# m2_emmc.net
KiCad netlist of a schematic drawn in Altium Designer
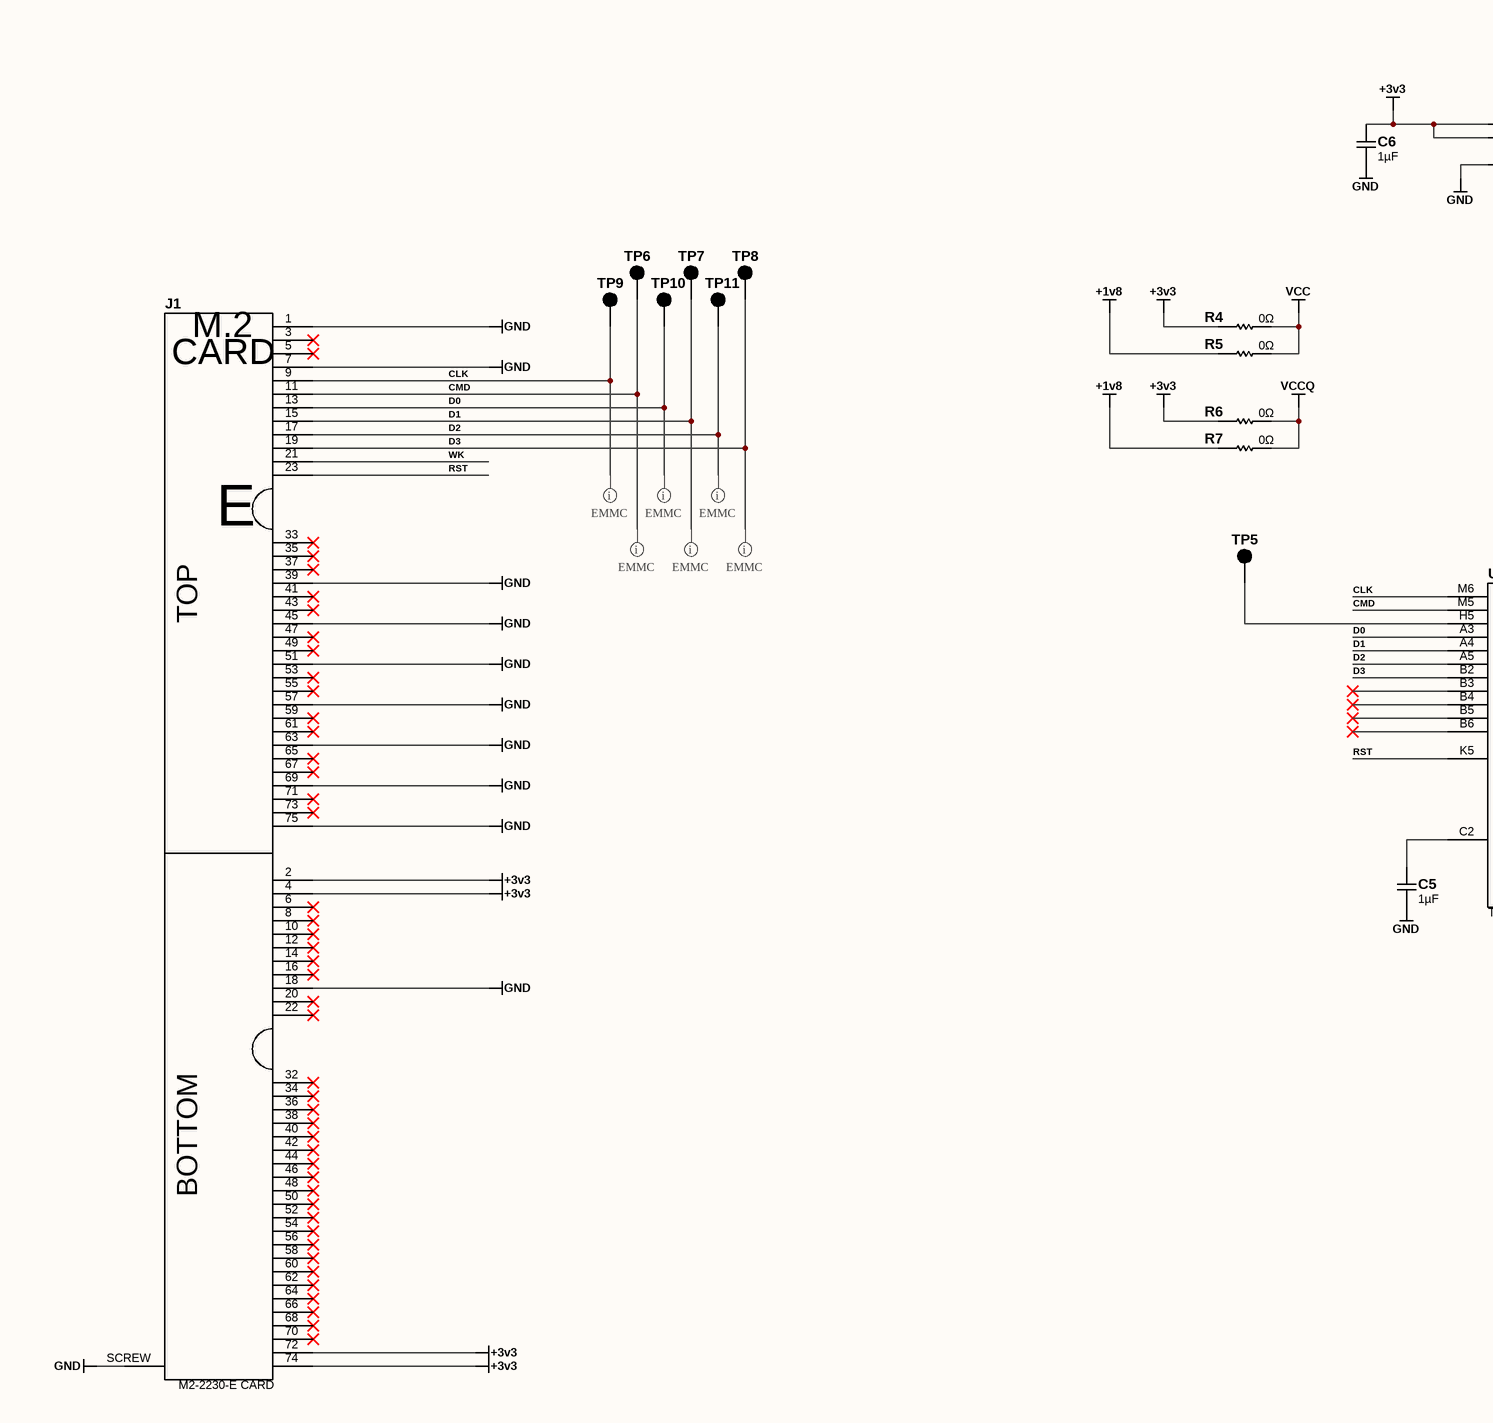
[diagram p0: m2_emmc.SchDoc, top left]
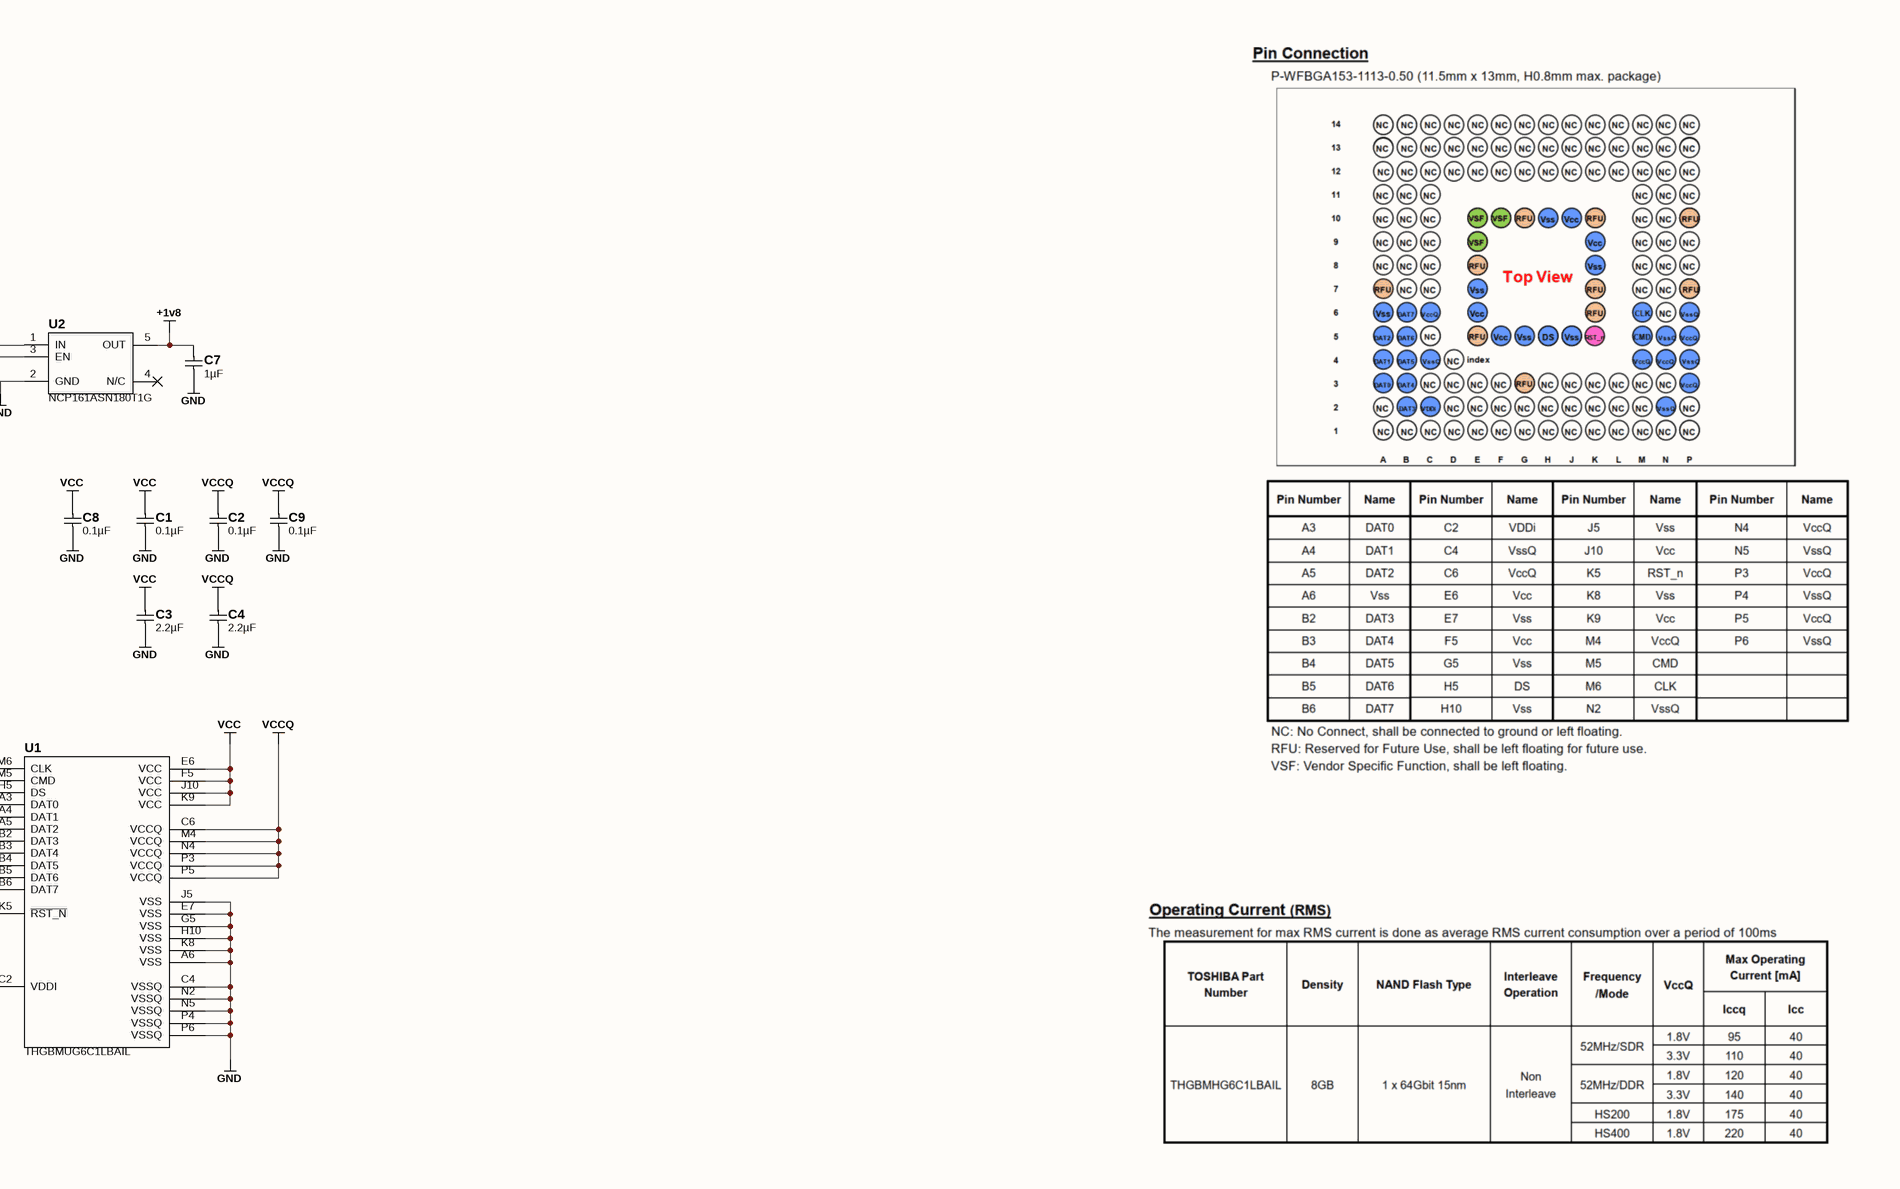
[diagram p1: m2_emmc.SchDoc, top right]
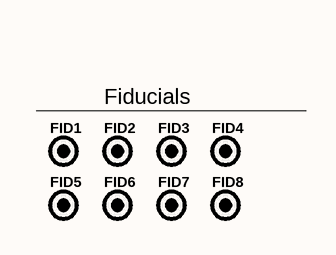
[diagram p2: m2_emmc.SchDoc, bottom left]
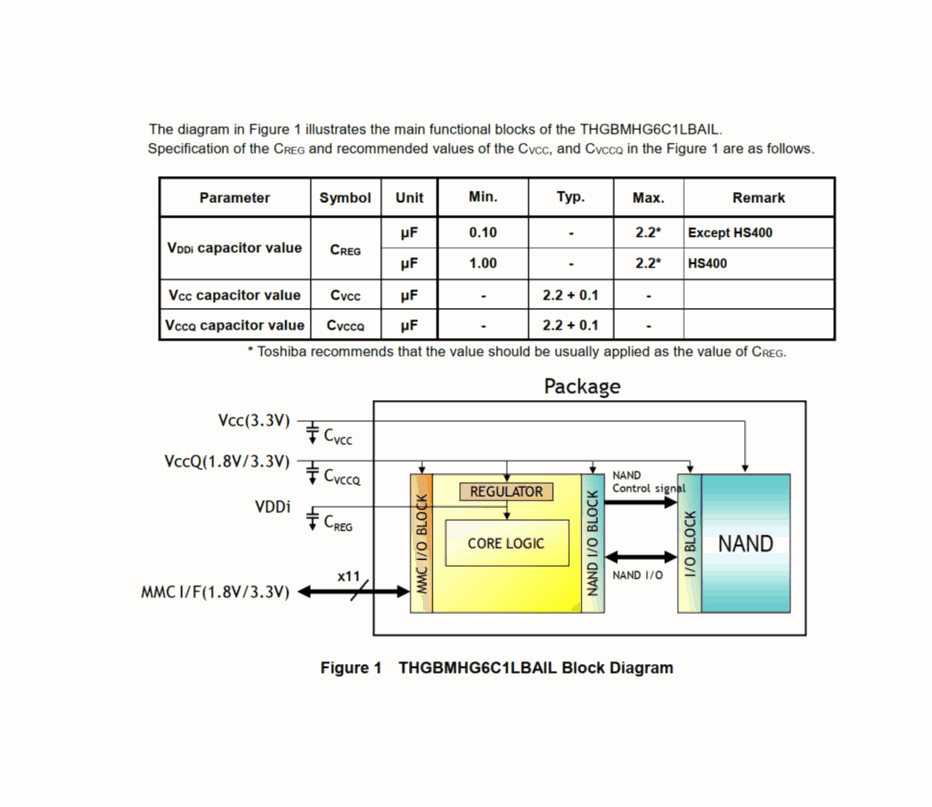
[diagram p3: m2_emmc.SchDoc, bottom right]

(export (version "E")
  (design (tool "Eeschema 10.0.6"))
  (components
    (comp (ref "C1")
      (value "0.1µF")
      (footprint "C0603_0.90MM_HD")
      (description "CAP CER 0.1UF 16V X7R 0603")
      (fields (field (name "INTERNAL PART NUMBER") "nan") (field (name "MANUFACTURER") "Murata Electronics"))
      (libsource (lib "capacitors") (part "C_2P_NP"))
    )
    (comp (ref "C2")
      (value "0.1µF")
      (footprint "C0603_0.90MM_HD")
      (description "CAP CER 0.1UF 16V X7R 0603")
      (fields (field (name "INTERNAL PART NUMBER") "nan") (field (name "MANUFACTURER") "Murata Electronics"))
      (libsource (lib "capacitors") (part "C_2P_NP"))
    )
    (comp (ref "C3")
      (value "2.2µF")
      (footprint "C0603_0.90MM_HD")
      (description "CAP CER 2.2UF 6.3V X7R 0603")
      (fields (field (name "INTERNAL PART NUMBER") "nan") (field (name "MANUFACTURER") "Murata Electronics"))
      (libsource (lib "capacitors") (part "C_2P_NP"))
    )
    (comp (ref "C4")
      (value "2.2µF")
      (footprint "C0603_0.90MM_HD")
      (description "CAP CER 2.2UF 6.3V X7R 0603")
      (fields (field (name "INTERNAL PART NUMBER") "nan") (field (name "MANUFACTURER") "Murata Electronics"))
      (libsource (lib "capacitors") (part "C_2P_NP"))
    )
    (comp (ref "C5")
      (value "1µF")
      (footprint "C0603_0.90MM_HD")
      (description "CAP CER 1UF 16V X7R 0603")
      (fields (field (name "INTERNAL PART NUMBER") "nan") (field (name "MANUFACTURER") "Murata Electronics"))
      (libsource (lib "capacitors") (part "C_2P_NP"))
    )
    (comp (ref "C6")
      (value "1µF")
      (footprint "C0603_0.90MM_HD")
      (description "CAP CER 1UF 16V X7R 0603")
      (fields (field (name "INTERNAL PART NUMBER") "nan") (field (name "MANUFACTURER") "Murata Electronics"))
      (libsource (lib "capacitors") (part "C_2P_NP"))
    )
    (comp (ref "C7")
      (value "1µF")
      (footprint "C0603_0.90MM_HD")
      (description "CAP CER 1UF 16V X7R 0603")
      (fields (field (name "INTERNAL PART NUMBER") "nan") (field (name "MANUFACTURER") "Murata Electronics"))
      (libsource (lib "capacitors") (part "C_2P_NP"))
    )
    (comp (ref "C8")
      (value "0.1µF")
      (footprint "C0603_0.90MM_HD")
      (description "CAP CER 0.1UF 16V X7R 0603")
      (fields (field (name "INTERNAL PART NUMBER") "nan") (field (name "MANUFACTURER") "Murata Electronics"))
      (libsource (lib "capacitors") (part "C_2P_NP"))
    )
    (comp (ref "C9")
      (value "0.1µF")
      (footprint "C0603_0.90MM_HD")
      (description "CAP CER 0.1UF 16V X7R 0603")
      (fields (field (name "INTERNAL PART NUMBER") "nan") (field (name "MANUFACTURER") "Murata Electronics"))
      (libsource (lib "capacitors") (part "C_2P_NP"))
    )
    (comp (ref "FID1")
      (value "fiducial-1mm-2mm")
      (footprint "fiducial-1mm-2mm")
      (fields (field (name "MANUFACTURER") "Wavenumber"))
      (libsource (lib "misc") (part "Fiducial"))
    )
    (comp (ref "FID2")
      (value "fiducial-1mm-2mm")
      (footprint "fiducial-1mm-2mm")
      (fields (field (name "MANUFACTURER") "Wavenumber"))
      (libsource (lib "misc") (part "Fiducial"))
    )
    (comp (ref "FID3")
      (value "fiducial-1mm-2mm")
      (footprint "fiducial-1mm-2mm")
      (fields (field (name "MANUFACTURER") "Wavenumber"))
      (libsource (lib "misc") (part "Fiducial"))
    )
    (comp (ref "FID4")
      (value "fiducial-1mm-2mm")
      (footprint "fiducial-1mm-2mm")
      (fields (field (name "MANUFACTURER") "Wavenumber"))
      (libsource (lib "misc") (part "Fiducial"))
    )
    (comp (ref "FID5")
      (value "fiducial-1mm-2mm")
      (footprint "fiducial-1mm-2mm")
      (fields (field (name "MANUFACTURER") "Wavenumber"))
      (libsource (lib "misc") (part "Fiducial"))
    )
    (comp (ref "FID6")
      (value "fiducial-1mm-2mm")
      (footprint "fiducial-1mm-2mm")
      (fields (field (name "MANUFACTURER") "Wavenumber"))
      (libsource (lib "misc") (part "Fiducial"))
    )
    (comp (ref "FID7")
      (value "fiducial-1mm-2mm")
      (footprint "fiducial-1mm-2mm")
      (fields (field (name "MANUFACTURER") "Wavenumber"))
      (libsource (lib "misc") (part "Fiducial"))
    )
    (comp (ref "FID8")
      (value "fiducial-1mm-2mm")
      (footprint "fiducial-1mm-2mm")
      (fields (field (name "MANUFACTURER") "Wavenumber"))
      (libsource (lib "misc") (part "Fiducial"))
    )
    (comp (ref "J1")
      (value "M2-2230-E CARD")
      (footprint "M2-2230-E")
      (description "M.2 2230 E Key Card Template")
      (fields (field (name "MANUFACTURER") "Wavenumber"))
      (libsource (lib "module") (part "M2_CARD__E"))
    )
    (comp (ref "R4")
      (value "0Ω")
      (footprint "R0603_0.55MM_HD")
      (description "RES 0.0 OHM 1/10W JUMP 0603 SMD")
      (fields
        (field (name "INTERNAL PART NUMBER") "nan")
        (field (name "MANUFACTURER") "Panasonic Electronic Components")
      )
      (libsource (lib "resistor_jellybean") (part "R_2P"))
    )
    (comp (ref "R5")
      (value "0Ω")
      (footprint "R0603_0.55MM_HD")
      (description "RES 0.0 OHM 1/10W JUMP 0603 SMD")
      (fields
        (field (name "INTERNAL PART NUMBER") "nan")
        (field (name "MANUFACTURER") "Panasonic Electronic Components")
      )
      (libsource (lib "resistor_jellybean") (part "R_2P"))
    )
    (comp (ref "R6")
      (value "0Ω")
      (footprint "R0603_0.55MM_HD")
      (description "RES 0.0 OHM 1/10W JUMP 0603 SMD")
      (fields
        (field (name "INTERNAL PART NUMBER") "nan")
        (field (name "MANUFACTURER") "Panasonic Electronic Components")
      )
      (libsource (lib "resistor_jellybean") (part "R_2P"))
    )
    (comp (ref "R7")
      (value "0Ω")
      (footprint "R0603_0.55MM_HD")
      (description "RES 0.0 OHM 1/10W JUMP 0603 SMD")
      (fields
        (field (name "INTERNAL PART NUMBER") "nan")
        (field (name "MANUFACTURER") "Panasonic Electronic Components")
      )
      (libsource (lib "resistor_jellybean") (part "R_2P"))
    )
    (comp (ref "TP5")
      (value "SMT Testpoint 20mil")
      (footprint "SMT_TP-25")
      (fields
        (field (name "MANUFACTURER PART NUMBER") "SMT_TP-25")
        (field (name "MANUFACTURER") "Wavenumber")
      )
      (libsource (lib "misc") (part "SMT_TEST"))
    )
    (comp (ref "TP6")
      (value "SMT Testpoint 20mil")
      (footprint "SMT_TP-25")
      (fields
        (field (name "MANUFACTURER PART NUMBER") "SMT_TP-25")
        (field (name "MANUFACTURER") "Wavenumber")
      )
      (libsource (lib "misc") (part "SMT_TEST"))
    )
    (comp (ref "TP7")
      (value "SMT Testpoint 20mil")
      (footprint "SMT_TP-25")
      (fields
        (field (name "MANUFACTURER PART NUMBER") "SMT_TP-25")
        (field (name "MANUFACTURER") "Wavenumber")
      )
      (libsource (lib "misc") (part "SMT_TEST"))
    )
    (comp (ref "TP8")
      (value "SMT Testpoint 20mil")
      (footprint "SMT_TP-25")
      (fields
        (field (name "MANUFACTURER PART NUMBER") "SMT_TP-25")
        (field (name "MANUFACTURER") "Wavenumber")
      )
      (libsource (lib "misc") (part "SMT_TEST"))
    )
    (comp (ref "TP9")
      (value "SMT Testpoint 20mil")
      (footprint "SMT_TP-25")
      (fields
        (field (name "MANUFACTURER PART NUMBER") "SMT_TP-25")
        (field (name "MANUFACTURER") "Wavenumber")
      )
      (libsource (lib "misc") (part "SMT_TEST"))
    )
    (comp (ref "TP10")
      (value "SMT Testpoint 20mil")
      (footprint "SMT_TP-25")
      (fields
        (field (name "MANUFACTURER PART NUMBER") "SMT_TP-25")
        (field (name "MANUFACTURER") "Wavenumber")
      )
      (libsource (lib "misc") (part "SMT_TEST"))
    )
    (comp (ref "TP11")
      (value "SMT Testpoint 20mil")
      (footprint "SMT_TP-25")
      (fields
        (field (name "MANUFACTURER PART NUMBER") "SMT_TP-25")
        (field (name "MANUFACTURER") "Wavenumber")
      )
      (libsource (lib "misc") (part "SMT_TEST"))
    )
    (comp (ref "U1")
      (value "THGBMUG6C1LBAIL")
      (footprint "BGA153C50P14X14_1150X1300X80")
      (description "eMMC 8GB v5.1 eMMC")
      (fields
        (field (name "MANUFACTURER") "Kioxia America")
        (field (name "JLCPCB PART #") "C7509349")
        (field (name "CREATED BY") "JSA")
      )
      (libsource (lib "ic") (part "EMMC-Generic"))
    )
    (comp (ref "U2")
      (value "NCP161ASN180T1G")
      (footprint "SOT23-5")
      (description "IC REG LINEAR 1.8V 450MA SOT23-5")
      (fields (field (name "MANUFACTURER") "onsemi") (field (name "JLCPCB PART #") "C22435172"))
      (libsource (lib "ic") (part "NCP161"))
    )
  )
  (nets
    (net (code "1") (name "+1v8") (class "Default")
      (node (ref "C7") (pin "2") (pinfunction "1_2") (pintype "passive"))
      (node (ref "R5") (pin "1") (pinfunction "1_1") (pintype "passive"))
      (node (ref "R7") (pin "1") (pinfunction "1_1") (pintype "passive"))
      (node (ref "U2") (pin "5") (pinfunction "OUT_5") (pintype "passive"))
    )
    (net (code "2") (name "+3v3") (class "Default")
      (node (ref "C6") (pin "2") (pinfunction "1_2") (pintype "passive"))
      (node (ref "J1") (pin "2") (pinfunction "2_2") (pintype "passive"))
      (node (ref "J1") (pin "4") (pinfunction "4_4") (pintype "passive"))
      (node (ref "J1") (pin "72") (pinfunction "72_72") (pintype "passive"))
      (node (ref "J1") (pin "74") (pinfunction "74_74") (pintype "passive"))
      (node (ref "R4") (pin "1") (pinfunction "1_1") (pintype "passive"))
      (node (ref "R6") (pin "1") (pinfunction "1_1") (pintype "passive"))
      (node (ref "U2") (pin "1") (pinfunction "IN_1") (pintype "passive"))
      (node (ref "U2") (pin "3") (pinfunction "EN_3") (pintype "passive"))
    )
    (net (code "3") (name "/CLK") (class "Default")
      (node (ref "J1") (pin "9") (pinfunction "9_9") (pintype "passive"))
      (node (ref "TP9") (pin "1") (pinfunction "1_1") (pintype "passive"))
      (node (ref "U1") (pin "M6") (pinfunction "CLK_M6") (pintype "passive"))
    )
    (net (code "4") (name "/CMD") (class "Default")
      (node (ref "J1") (pin "11") (pinfunction "11_11") (pintype "passive"))
      (node (ref "TP6") (pin "1") (pinfunction "1_1") (pintype "passive"))
      (node (ref "U1") (pin "M5") (pinfunction "CMD_M5") (pintype "passive"))
    )
    (net (code "5") (name "/D0") (class "Default")
      (node (ref "J1") (pin "13") (pinfunction "13_13") (pintype "passive"))
      (node (ref "TP10") (pin "1") (pinfunction "1_1") (pintype "passive"))
      (node (ref "U1") (pin "A3") (pinfunction "DAT0_A3") (pintype "passive"))
    )
    (net (code "6") (name "/D1") (class "Default")
      (node (ref "J1") (pin "15") (pinfunction "15_15") (pintype "passive"))
      (node (ref "TP7") (pin "1") (pinfunction "1_1") (pintype "passive"))
      (node (ref "U1") (pin "A4") (pinfunction "DAT1_A4") (pintype "passive"))
    )
    (net (code "7") (name "/D2") (class "Default")
      (node (ref "J1") (pin "17") (pinfunction "17_17") (pintype "passive"))
      (node (ref "TP11") (pin "1") (pinfunction "1_1") (pintype "passive"))
      (node (ref "U1") (pin "A5") (pinfunction "DAT2_A5") (pintype "passive"))
    )
    (net (code "8") (name "/D3") (class "Default")
      (node (ref "J1") (pin "19") (pinfunction "19_19") (pintype "passive"))
      (node (ref "TP8") (pin "1") (pinfunction "1_1") (pintype "passive"))
      (node (ref "U1") (pin "B2") (pinfunction "DAT3_B2") (pintype "passive"))
    )
    (net (code "9") (name "/RST") (class "Default")
      (node (ref "J1") (pin "23") (pinfunction "23_23") (pintype "passive"))
      (node (ref "U1") (pin "K5") (pinfunction "~{RST_N}_K5") (pintype "passive"))
    )
    (net (code "10") (name "/WK") (class "Default")
      (node (ref "J1") (pin "21") (pinfunction "21_21") (pintype "passive"))
    )
    (net (code "11") (name "GND") (class "Default")
      (node (ref "C1") (pin "1") (pinfunction "1_1") (pintype "passive"))
      (node (ref "C2") (pin "1") (pinfunction "1_1") (pintype "passive"))
      (node (ref "C3") (pin "1") (pinfunction "1_1") (pintype "passive"))
      (node (ref "C4") (pin "1") (pinfunction "1_1") (pintype "passive"))
      (node (ref "C5") (pin "1") (pinfunction "1_1") (pintype "passive"))
      (node (ref "C6") (pin "1") (pinfunction "1_1") (pintype "passive"))
      (node (ref "C7") (pin "1") (pinfunction "1_1") (pintype "passive"))
      (node (ref "C8") (pin "1") (pinfunction "1_1") (pintype "passive"))
      (node (ref "C9") (pin "1") (pinfunction "1_1") (pintype "passive"))
      (node (ref "J1") (pin "1") (pinfunction "1_1") (pintype "passive"))
      (node (ref "J1") (pin "18") (pinfunction "18_18") (pintype "passive"))
      (node (ref "J1") (pin "39") (pinfunction "39_39") (pintype "passive"))
      (node (ref "J1") (pin "45") (pinfunction "45_45") (pintype "passive"))
      (node (ref "J1") (pin "51") (pinfunction "51_51") (pintype "passive"))
      (node (ref "J1") (pin "57") (pinfunction "57_57") (pintype "passive"))
      (node (ref "J1") (pin "63") (pinfunction "63_63") (pintype "passive"))
      (node (ref "J1") (pin "69") (pinfunction "69_69") (pintype "passive"))
      (node (ref "J1") (pin "7") (pinfunction "7_7") (pintype "passive"))
      (node (ref "J1") (pin "75") (pinfunction "75_75") (pintype "passive"))
      (node (ref "J1") (pin "SCREW") (pinfunction "SCREW_SCREW") (pintype "passive"))
      (node (ref "U1") (pin "A6") (pinfunction "VSS_A6") (pintype "passive"))
      (node (ref "U1") (pin "C4") (pinfunction "VSSQ_C4") (pintype "passive"))
      (node (ref "U1") (pin "E7") (pinfunction "VSS_E7") (pintype "passive"))
      (node (ref "U1") (pin "G5") (pinfunction "VSS_G5") (pintype "passive"))
      (node (ref "U1") (pin "H10") (pinfunction "VSS_H10") (pintype "passive"))
      (node (ref "U1") (pin "J5") (pinfunction "VSS_J5") (pintype "passive"))
      (node (ref "U1") (pin "K8") (pinfunction "VSS_K8") (pintype "passive"))
      (node (ref "U1") (pin "N2") (pinfunction "VSSQ_N2") (pintype "passive"))
      (node (ref "U1") (pin "N5") (pinfunction "VSSQ_N5") (pintype "passive"))
      (node (ref "U1") (pin "P4") (pinfunction "VSSQ_P4") (pintype "passive"))
      (node (ref "U1") (pin "P6") (pinfunction "VSSQ_P6") (pintype "passive"))
      (node (ref "U2") (pin "2") (pinfunction "GND_2") (pintype "passive"))
    )
    (net (code "12") (name "Net-(U1-DS)") (class "Default")
      (node (ref "TP5") (pin "1") (pinfunction "1_1") (pintype "passive"))
      (node (ref "U1") (pin "H5") (pinfunction "DS_H5") (pintype "passive"))
    )
    (net (code "13") (name "Net-(U1-VDDI)") (class "Default")
      (node (ref "C5") (pin "2") (pinfunction "1_2") (pintype "passive"))
      (node (ref "U1") (pin "C2") (pinfunction "VDDI_C2") (pintype "passive"))
    )
    (net (code "14") (name "VCC") (class "Default")
      (node (ref "C1") (pin "2") (pinfunction "1_2") (pintype "passive"))
      (node (ref "C3") (pin "2") (pinfunction "1_2") (pintype "passive"))
      (node (ref "C8") (pin "2") (pinfunction "1_2") (pintype "passive"))
      (node (ref "R4") (pin "2") (pinfunction "2_2") (pintype "passive"))
      (node (ref "R5") (pin "2") (pinfunction "2_2") (pintype "passive"))
      (node (ref "U1") (pin "E6") (pinfunction "VCC_E6") (pintype "passive"))
      (node (ref "U1") (pin "F5") (pinfunction "VCC_F5") (pintype "passive"))
      (node (ref "U1") (pin "J10") (pinfunction "VCC_J10") (pintype "passive"))
      (node (ref "U1") (pin "K9") (pinfunction "VCC_K9") (pintype "passive"))
    )
    (net (code "15") (name "VCCQ") (class "Default")
      (node (ref "C2") (pin "2") (pinfunction "1_2") (pintype "passive"))
      (node (ref "C4") (pin "2") (pinfunction "1_2") (pintype "passive"))
      (node (ref "C9") (pin "2") (pinfunction "1_2") (pintype "passive"))
      (node (ref "R6") (pin "2") (pinfunction "2_2") (pintype "passive"))
      (node (ref "R7") (pin "2") (pinfunction "2_2") (pintype "passive"))
      (node (ref "U1") (pin "C6") (pinfunction "VCCQ_C6") (pintype "passive"))
      (node (ref "U1") (pin "M4") (pinfunction "VCCQ_M4") (pintype "passive"))
      (node (ref "U1") (pin "N4") (pinfunction "VCCQ_N4") (pintype "passive"))
      (node (ref "U1") (pin "P3") (pinfunction "VCCQ_P3") (pintype "passive"))
      (node (ref "U1") (pin "P5") (pinfunction "VCCQ_P5") (pintype "passive"))
    )
    (net (code "16") (name "unconnected-(J1-Pad3)") (class "Default")
      (node (ref "J1") (pin "3") (pinfunction "3_3") (pintype "passive+no_connect"))
    )
    (net (code "17") (name "unconnected-(J1-Pad5)") (class "Default")
      (node (ref "J1") (pin "5") (pinfunction "5_5") (pintype "passive+no_connect"))
    )
    (net (code "18") (name "unconnected-(J1-Pad6)") (class "Default")
      (node (ref "J1") (pin "6") (pinfunction "6_6") (pintype "passive+no_connect"))
    )
    (net (code "19") (name "unconnected-(J1-Pad8)") (class "Default")
      (node (ref "J1") (pin "8") (pinfunction "8_8") (pintype "passive+no_connect"))
    )
    (net (code "20") (name "unconnected-(J1-Pad10)") (class "Default")
      (node (ref "J1") (pin "10") (pinfunction "10_10") (pintype "passive+no_connect"))
    )
    (net (code "21") (name "unconnected-(J1-Pad12)") (class "Default")
      (node (ref "J1") (pin "12") (pinfunction "12_12") (pintype "passive+no_connect"))
    )
    (net (code "22") (name "unconnected-(J1-Pad14)") (class "Default")
      (node (ref "J1") (pin "14") (pinfunction "14_14") (pintype "passive+no_connect"))
    )
    (net (code "23") (name "unconnected-(J1-Pad16)") (class "Default")
      (node (ref "J1") (pin "16") (pinfunction "16_16") (pintype "passive+no_connect"))
    )
    (net (code "24") (name "unconnected-(J1-Pad20)") (class "Default")
      (node (ref "J1") (pin "20") (pinfunction "20_20") (pintype "passive+no_connect"))
    )
    (net (code "25") (name "unconnected-(J1-Pad22)") (class "Default")
      (node (ref "J1") (pin "22") (pinfunction "22_22") (pintype "passive+no_connect"))
    )
    (net (code "26") (name "unconnected-(J1-Pad32)") (class "Default")
      (node (ref "J1") (pin "32") (pinfunction "32_32") (pintype "passive+no_connect"))
    )
    (net (code "27") (name "unconnected-(J1-Pad33)") (class "Default")
      (node (ref "J1") (pin "33") (pinfunction "33_33") (pintype "passive+no_connect"))
    )
    (net (code "28") (name "unconnected-(J1-Pad34)") (class "Default")
      (node (ref "J1") (pin "34") (pinfunction "34_34") (pintype "passive+no_connect"))
    )
    (net (code "29") (name "unconnected-(J1-Pad35)") (class "Default")
      (node (ref "J1") (pin "35") (pinfunction "35_35") (pintype "passive+no_connect"))
    )
    (net (code "30") (name "unconnected-(J1-Pad36)") (class "Default")
      (node (ref "J1") (pin "36") (pinfunction "36_36") (pintype "passive+no_connect"))
    )
    (net (code "31") (name "unconnected-(J1-Pad37)") (class "Default")
      (node (ref "J1") (pin "37") (pinfunction "37_37") (pintype "passive+no_connect"))
    )
    (net (code "32") (name "unconnected-(J1-Pad38)") (class "Default")
      (node (ref "J1") (pin "38") (pinfunction "38_38") (pintype "passive+no_connect"))
    )
    (net (code "33") (name "unconnected-(J1-Pad40)") (class "Default")
      (node (ref "J1") (pin "40") (pinfunction "40_40") (pintype "passive+no_connect"))
    )
    (net (code "34") (name "unconnected-(J1-Pad41)") (class "Default")
      (node (ref "J1") (pin "41") (pinfunction "41_41") (pintype "passive+no_connect"))
    )
    (net (code "35") (name "unconnected-(J1-Pad42)") (class "Default")
      (node (ref "J1") (pin "42") (pinfunction "42_42") (pintype "passive+no_connect"))
    )
    (net (code "36") (name "unconnected-(J1-Pad43)") (class "Default")
      (node (ref "J1") (pin "43") (pinfunction "43_43") (pintype "passive+no_connect"))
    )
    (net (code "37") (name "unconnected-(J1-Pad44)") (class "Default")
      (node (ref "J1") (pin "44") (pinfunction "44_44") (pintype "passive+no_connect"))
    )
    (net (code "38") (name "unconnected-(J1-Pad46)") (class "Default")
      (node (ref "J1") (pin "46") (pinfunction "46_46") (pintype "passive+no_connect"))
    )
    (net (code "39") (name "unconnected-(J1-Pad47)") (class "Default")
      (node (ref "J1") (pin "47") (pinfunction "47_47") (pintype "passive+no_connect"))
    )
    (net (code "40") (name "unconnected-(J1-Pad48)") (class "Default")
      (node (ref "J1") (pin "48") (pinfunction "48_48") (pintype "passive+no_connect"))
    )
    (net (code "41") (name "unconnected-(J1-Pad49)") (class "Default")
      (node (ref "J1") (pin "49") (pinfunction "49_49") (pintype "passive+no_connect"))
    )
    (net (code "42") (name "unconnected-(J1-Pad50)") (class "Default")
      (node (ref "J1") (pin "50") (pinfunction "50_50") (pintype "passive+no_connect"))
    )
    (net (code "43") (name "unconnected-(J1-Pad52)") (class "Default")
      (node (ref "J1") (pin "52") (pinfunction "52_52") (pintype "passive+no_connect"))
    )
    (net (code "44") (name "unconnected-(J1-Pad53)") (class "Default")
      (node (ref "J1") (pin "53") (pinfunction "53_53") (pintype "passive+no_connect"))
    )
    (net (code "45") (name "unconnected-(J1-Pad54)") (class "Default")
      (node (ref "J1") (pin "54") (pinfunction "54_54") (pintype "passive+no_connect"))
    )
    (net (code "46") (name "unconnected-(J1-Pad55)") (class "Default")
      (node (ref "J1") (pin "55") (pinfunction "55_55") (pintype "passive+no_connect"))
    )
    (net (code "47") (name "unconnected-(J1-Pad56)") (class "Default")
      (node (ref "J1") (pin "56") (pinfunction "56_56") (pintype "passive+no_connect"))
    )
    (net (code "48") (name "unconnected-(J1-Pad58)") (class "Default")
      (node (ref "J1") (pin "58") (pinfunction "58_58") (pintype "passive+no_connect"))
    )
    (net (code "49") (name "unconnected-(J1-Pad59)") (class "Default")
      (node (ref "J1") (pin "59") (pinfunction "59_59") (pintype "passive+no_connect"))
    )
    (net (code "50") (name "unconnected-(J1-Pad60)") (class "Default")
      (node (ref "J1") (pin "60") (pinfunction "60_60") (pintype "passive+no_connect"))
    )
    (net (code "51") (name "unconnected-(J1-Pad61)") (class "Default")
      (node (ref "J1") (pin "61") (pinfunction "61_61") (pintype "passive+no_connect"))
    )
    (net (code "52") (name "unconnected-(J1-Pad62)") (class "Default")
      (node (ref "J1") (pin "62") (pinfunction "62_62") (pintype "passive+no_connect"))
    )
    (net (code "53") (name "unconnected-(J1-Pad64)") (class "Default")
      (node (ref "J1") (pin "64") (pinfunction "64_64") (pintype "passive+no_connect"))
    )
    (net (code "54") (name "unconnected-(J1-Pad65)") (class "Default")
      (node (ref "J1") (pin "65") (pinfunction "65_65") (pintype "passive+no_connect"))
    )
    (net (code "55") (name "unconnected-(J1-Pad66)") (class "Default")
      (node (ref "J1") (pin "66") (pinfunction "66_66") (pintype "passive+no_connect"))
    )
    (net (code "56") (name "unconnected-(J1-Pad67)") (class "Default")
      (node (ref "J1") (pin "67") (pinfunction "67_67") (pintype "passive+no_connect"))
    )
    (net (code "57") (name "unconnected-(J1-Pad68)") (class "Default")
      (node (ref "J1") (pin "68") (pinfunction "68_68") (pintype "passive+no_connect"))
    )
    (net (code "58") (name "unconnected-(J1-Pad70)") (class "Default")
      (node (ref "J1") (pin "70") (pinfunction "70_70") (pintype "passive+no_connect"))
    )
    (net (code "59") (name "unconnected-(J1-Pad71)") (class "Default")
      (node (ref "J1") (pin "71") (pinfunction "71_71") (pintype "passive+no_connect"))
    )
    (net (code "60") (name "unconnected-(J1-Pad73)") (class "Default")
      (node (ref "J1") (pin "73") (pinfunction "73_73") (pintype "passive+no_connect"))
    )
    (net (code "61") (name "unconnected-(U1-DAT4-PadB3)") (class "Default")
      (node (ref "U1") (pin "B3") (pinfunction "DAT4_B3") (pintype "passive+no_connect"))
    )
    (net (code "62") (name "unconnected-(U1-DAT5-PadB4)") (class "Default")
      (node (ref "U1") (pin "B4") (pinfunction "DAT5_B4") (pintype "passive+no_connect"))
    )
    (net (code "63") (name "unconnected-(U1-DAT6-PadB5)") (class "Default")
      (node (ref "U1") (pin "B5") (pinfunction "DAT6_B5") (pintype "passive+no_connect"))
    )
    (net (code "64") (name "unconnected-(U1-DAT7-PadB6)") (class "Default")
      (node (ref "U1") (pin "B6") (pinfunction "DAT7_B6") (pintype "passive+no_connect"))
    )
    (net (code "65") (name "unconnected-(U2-N{slash}C-Pad4)") (class "Default")
      (node (ref "U2") (pin "4") (pinfunction "N/C_4") (pintype "passive+no_connect"))
    )
  )
)
